# BlueStone_Terminal_V2_11.net
KiCad netlist of a schematic drawn in Altium Designer
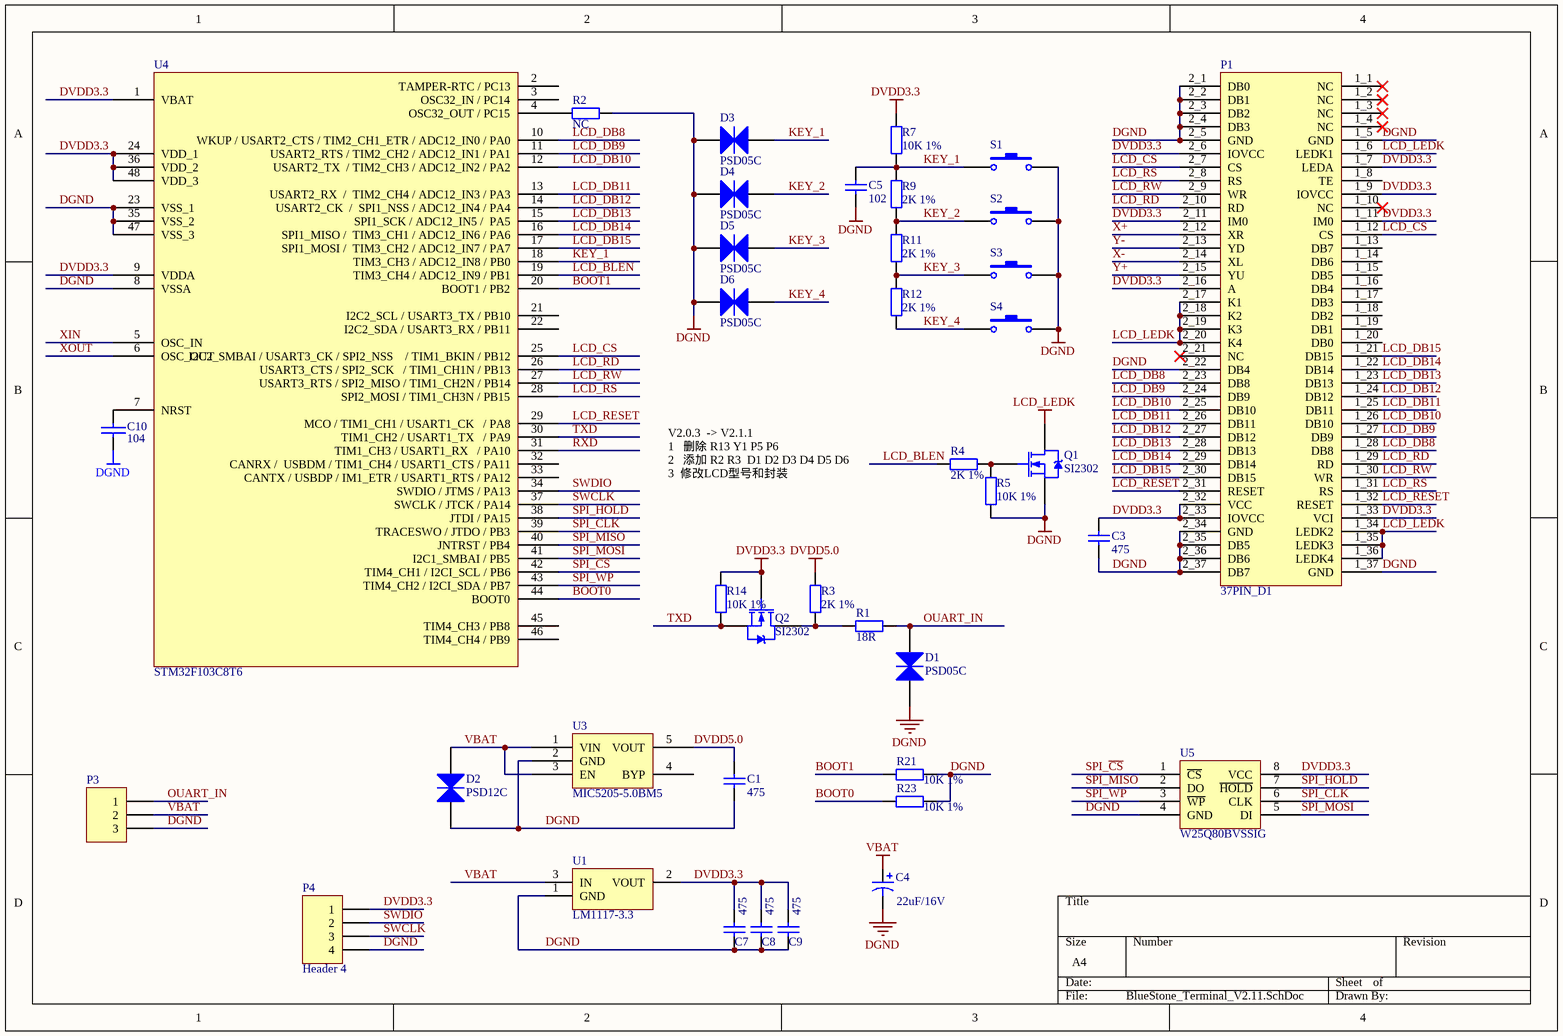
[diagram p0: BlueStone_Terminal_V2.11.SchDoc]

(export (version "E")
  (design (tool "Eeschema 10.0.6"))
  (components
    (comp (ref "C1")
      (value "475")
      (footprint "1608(0603C)")
      (description "Capacitor")
      (fields (field (name "PUBLISHER") "Altium Limited"))
      (libsource (lib "Miscellaneous Devices") (part "Cap"))
    )
    (comp (ref "C3")
      (value "475")
      (footprint "1608(0603C)")
      (description "Capacitor")
      (fields (field (name "PUBLISHER") "Altium Limited"))
      (libsource (lib "Miscellaneous Devices") (part "Cap"))
    )
    (comp (ref "C4")
      (value "22uF/16V")
      (footprint "3216(1206B)")
      (description "Polarized Capacitor (Radial)")
      (fields (field (name "PUBLISHER") "Altium Limited"))
      (libsource (lib "Miscellaneous Devices") (part "Cap Pol1"))
    )
    (comp (ref "C5")
      (value "102")
      (footprint "1608(0603C)")
      (description "Capacitor")
      (fields (field (name "PUBLISHER") "Altium Limited"))
      (libsource (lib "Miscellaneous Devices") (part "Cap"))
    )
    (comp (ref "C7")
      (value "475")
      (footprint "1608(0603C)")
      (description "Capacitor")
      (fields (field (name "PUBLISHER") "Altium Limited"))
      (libsource (lib "Miscellaneous Devices") (part "Cap"))
    )
    (comp (ref "C8")
      (value "475")
      (footprint "1608(0603C)")
      (description "Capacitor")
      (fields (field (name "PUBLISHER") "Altium Limited"))
      (libsource (lib "Miscellaneous Devices") (part "Cap"))
    )
    (comp (ref "C9")
      (value "475")
      (footprint "1608(0603C)")
      (description "Capacitor")
      (fields (field (name "PUBLISHER") "Altium Limited"))
      (libsource (lib "Miscellaneous Devices") (part "Cap"))
    )
    (comp (ref "C10")
      (value "104")
      (footprint "1608(0603C)")
      (description "Capacitor")
      (libsource (lib "*") (part "CAP"))
    )
    (comp (ref "D1")
      (value "PSD05C")
      (footprint "SOD523(0603R)")
      (description "Default Diode")
      (fields (field (name "PUBLISHER") "Altium Limited"))
      (libsource (lib "diodes") (part "RSBC6.8CS"))
    )
    (comp (ref "D2")
      (value "PSD12C")
      (footprint "SOD523(0603R)")
      (description "Default Diode")
      (fields (field (name "PUBLISHER") "Altium Limited"))
      (libsource (lib "diodes") (part "RSBC6.8CS"))
    )
    (comp (ref "D3")
      (value "PSD05C")
      (footprint "SOD523(0603R)")
      (description "Default Diode")
      (fields (field (name "PUBLISHER") "Altium Limited"))
      (libsource (lib "diodes") (part "RSBC6.8CS"))
    )
    (comp (ref "D4")
      (value "PSD05C")
      (footprint "SOD523(0603R)")
      (description "Default Diode")
      (fields (field (name "PUBLISHER") "Altium Limited"))
      (libsource (lib "diodes") (part "RSBC6.8CS"))
    )
    (comp (ref "D5")
      (value "PSD05C")
      (footprint "SOD523(0603R)")
      (description "Default Diode")
      (fields (field (name "PUBLISHER") "Altium Limited"))
      (libsource (lib "diodes") (part "RSBC6.8CS"))
    )
    (comp (ref "D6")
      (value "PSD05C")
      (footprint "SOD523(0603R)")
      (description "Default Diode")
      (fields (field (name "PUBLISHER") "Altium Limited"))
      (libsource (lib "diodes") (part "RSBC6.8CS"))
    )
    (comp (ref "P1") (value "37PIN_D1") (footprint "Z240_D1") (libsource (lib "LCD") (part "37PIN_D1")))
    (comp (ref "P3")
      (value "~")
      (footprint "SIP3")
      (description "Header, 3-Pin")
      (fields (field (name "PUBLISHER") "Altium Limited"))
      (libsource (lib "Miscellaneous Connectors") (part "Header 3"))
    )
    (comp (ref "P4")
      (value "Header 4")
      (footprint "HDR1X4")
      (description "Header, 4-Pin")
      (fields (field (name "PUBLISHER") "Altium Limited"))
      (libsource (lib "Miscellaneous Connectors") (part "Header 4"))
    )
    (comp (ref "Q1") (value "SI2302") (footprint "SOT-23") (libsource (lib "MosSCH") (part "NMOS  (SOT23)")))
    (comp (ref "Q2") (value "SI2302") (footprint "SOT-23") (libsource (lib "MosSCH") (part "NMOS  (SOT23)")))
    (comp (ref "R1")
      (value "18R")
      (footprint "1608(0603R)")
      (description "Resistor")
      (fields (field (name "PUBLISHER") "Altium Limited"))
      (libsource (lib "Miscellaneous Devices") (part "Res2"))
    )
    (comp (ref "R2")
      (value "NC")
      (footprint "1608(0603R)")
      (description "Resistor")
      (fields (field (name "PUBLISHER") "Altium Limited"))
      (libsource (lib "") (part "Res2_3"))
    )
    (comp (ref "R3")
      (value "2K 1%")
      (footprint "1608(0603R)")
      (description "Resistor")
      (fields (field (name "PUBLISHER") "Altium Limited"))
      (libsource (lib "") (part "Res2_2"))
    )
    (comp (ref "R4")
      (value "2K 1%")
      (footprint "1608(0603R)")
      (description "Resistor")
      (fields (field (name "PUBLISHER") "Altium Limited"))
      (libsource (lib "Miscellaneous Devices") (part "Res2"))
    )
    (comp (ref "R5")
      (value "10K 1%")
      (footprint "1608(0603R)")
      (description "Resistor")
      (fields (field (name "PUBLISHER") "Altium Limited"))
      (libsource (lib "") (part "Res2_2"))
    )
    (comp (ref "R7")
      (value "10K 1%")
      (footprint "1608(0603R)")
      (description "Resistor")
      (fields (field (name "PUBLISHER") "Altium Limited"))
      (libsource (lib "") (part "Res2_1"))
    )
    (comp (ref "R9")
      (value "2K 1%")
      (footprint "1608(0603R)")
      (description "Resistor")
      (fields (field (name "PUBLISHER") "Altium Limited"))
      (libsource (lib "") (part "Res2_1"))
    )
    (comp (ref "R11")
      (value "2K 1%")
      (footprint "1608(0603R)")
      (description "Resistor")
      (fields (field (name "PUBLISHER") "Altium Limited"))
      (libsource (lib "") (part "Res2_1"))
    )
    (comp (ref "R12")
      (value "2K 1%")
      (footprint "1608(0603R)")
      (description "Resistor")
      (fields (field (name "PUBLISHER") "Altium Limited"))
      (libsource (lib "") (part "Res2_1"))
    )
    (comp (ref "R14")
      (value "10K 1%")
      (footprint "1608(0603R)")
      (description "Resistor")
      (fields (field (name "PUBLISHER") "Altium Limited"))
      (libsource (lib "") (part "Res2_2"))
    )
    (comp (ref "R21")
      (value "10K 1%")
      (footprint "1608(0603R)")
      (description "Resistor")
      (fields (field (name "PUBLISHER") "Altium Limited"))
      (libsource (lib "") (part "Res2_3"))
    )
    (comp (ref "R23")
      (value "10K 1%")
      (footprint "1608(0603R)")
      (description "Resistor")
      (fields (field (name "PUBLISHER") "Altium Limited"))
      (libsource (lib "") (part "Res2_3"))
    )
    (comp (ref "S1")
      (value "~")
      (footprint "KEY-3")
      (description "Switch")
      (fields (field (name "PUBLISHER") "Altium Limited"))
      (libsource (lib "Miscellaneous Devices") (part "SW-PB"))
    )
    (comp (ref "S2")
      (value "~")
      (footprint "KEY-3")
      (description "Switch")
      (fields (field (name "PUBLISHER") "Altium Limited"))
      (libsource (lib "Miscellaneous Devices") (part "SW-PB"))
    )
    (comp (ref "S3")
      (value "~")
      (footprint "KEY-3")
      (description "Switch")
      (fields (field (name "PUBLISHER") "Altium Limited"))
      (libsource (lib "Miscellaneous Devices") (part "SW-PB"))
    )
    (comp (ref "S4")
      (value "~")
      (footprint "KEY-3")
      (description "Switch")
      (fields (field (name "PUBLISHER") "Altium Limited"))
      (libsource (lib "Miscellaneous Devices") (part "SW-PB"))
    )
    (comp (ref "U1") (value "LM1117-3.3") (footprint "SOT-223") (libsource (lib "power") (part "LM1117")))
    (comp (ref "U3")
      (value "MIC5205-5.0BM5")
      (footprint "SOT23-5")
      (libsource (lib "power") (part "MIC5205"))
    )
    (comp (ref "U4") (value "STM32F103C8T6") (footprint "LQFP48_N") (libsource (lib "*") (part "STM32F103C")))
    (comp (ref "U5")
      (value "W25Q80BVSSIG")
      (footprint "SO-8(Width: 7.8mm)")
      (libsource (lib "MySCH") (part "W55X16"))
    )
  )
  (nets
    (net (code "1") (name "/BOOT0") (class "Default")
      (node (ref "R23") (pin "1") (pinfunction "1_1") (pintype "passive"))
      (node (ref "U4") (pin "44") (pinfunction "BOOT0_44") (pintype "passive"))
    )
    (net (code "2") (name "/BOOT1") (class "Default")
      (node (ref "R21") (pin "1") (pinfunction "1_1") (pintype "passive"))
      (node (ref "U4") (pin "20") (pinfunction "BOOT1_/_PB2_20") (pintype "passive"))
    )
    (net (code "3") (name "/KEY_1") (class "Default")
      (node (ref "C5") (pin "1") (pinfunction "1_1") (pintype "passive"))
      (node (ref "D3") (pin "2") (pinfunction "K_2") (pintype "passive"))
      (node (ref "R7") (pin "2") (pinfunction "2_2") (pintype "passive"))
      (node (ref "R9") (pin "1") (pinfunction "1_1") (pintype "passive"))
      (node (ref "S1") (pin "1") (pinfunction "1_1") (pintype "passive"))
      (node (ref "U4") (pin "18") (pinfunction "TIM3_CH3_/_ADC12_IN8_/_PB0_18") (pintype "passive"))
    )
    (net (code "4") (name "/KEY_2") (class "Default")
      (node (ref "D4") (pin "2") (pinfunction "K_2") (pintype "passive"))
      (node (ref "R11") (pin "1") (pinfunction "1_1") (pintype "passive"))
      (node (ref "R9") (pin "2") (pinfunction "2_2") (pintype "passive"))
      (node (ref "S2") (pin "1") (pinfunction "1_1") (pintype "passive"))
    )
    (net (code "5") (name "/KEY_3") (class "Default")
      (node (ref "D5") (pin "2") (pinfunction "K_2") (pintype "passive"))
      (node (ref "R11") (pin "2") (pinfunction "2_2") (pintype "passive"))
      (node (ref "R12") (pin "1") (pinfunction "1_1") (pintype "passive"))
      (node (ref "S3") (pin "1") (pinfunction "1_1") (pintype "passive"))
    )
    (net (code "6") (name "/KEY_4") (class "Default")
      (node (ref "D6") (pin "2") (pinfunction "K_2") (pintype "passive"))
      (node (ref "R12") (pin "2") (pinfunction "2_2") (pintype "passive"))
      (node (ref "S4") (pin "1") (pinfunction "1_1") (pintype "passive"))
    )
    (net (code "7") (name "/LCD_BLEN") (class "Default")
      (node (ref "R4") (pin "2") (pinfunction "2_2") (pintype "passive"))
      (node (ref "U4") (pin "19") (pinfunction "TIM3_CH4_/_ADC12_IN9_/_PB1_19") (pintype "passive"))
    )
    (net (code "8") (name "/LCD_CS") (class "Default")
      (node (ref "P1") (pin "1_12") (pinfunction "CS_1_12") (pintype "passive"))
      (node (ref "P1") (pin "2_7") (pinfunction "CS_2_7") (pintype "passive"))
      (node (ref "U4") (pin "25") (pinfunction "I2C2_SMBAI_/_USART3_CK_/_SPI2_NSS____/_TIM1_BKIN_/_PB12_25") (pintype "passive"))
    )
    (net (code "9") (name "/LCD_DB8") (class "Default")
      (node (ref "P1") (pin "1_28") (pinfunction "DB8_1_28") (pintype "passive"))
      (node (ref "P1") (pin "2_23") (pinfunction "DB8_2_23") (pintype "passive"))
      (node (ref "U4") (pin "10") (pinfunction "WKUP_/_USART2_CTS_/_TIM2_CH1_ETR_/_ADC12_IN0_/_PA0_10") (pintype "passive"))
    )
    (net (code "10") (name "/LCD_DB9") (class "Default")
      (node (ref "P1") (pin "1_27") (pinfunction "DB9_1_27") (pintype "passive"))
      (node (ref "P1") (pin "2_24") (pinfunction "DB9_2_24") (pintype "passive"))
      (node (ref "U4") (pin "11") (pinfunction "USART2_RTS_/_TIM2_CH2_/_ADC12_IN1_/_PA1_11") (pintype "passive"))
    )
    (net (code "11") (name "/LCD_DB10") (class "Default")
      (node (ref "P1") (pin "1_26") (pinfunction "DB10_1_26") (pintype "passive"))
      (node (ref "P1") (pin "2_25") (pinfunction "DB10_2_25") (pintype "passive"))
      (node (ref "U4") (pin "12") (pinfunction "USART2_TX__/_TIM2_CH3_/_ADC12_IN2_/_PA2_12") (pintype "passive"))
    )
    (net (code "12") (name "/LCD_DB11") (class "Default")
      (node (ref "P1") (pin "1_25") (pinfunction "DB11_1_25") (pintype "passive"))
      (node (ref "P1") (pin "2_26") (pinfunction "DB11_2_26") (pintype "passive"))
      (node (ref "U4") (pin "13") (pinfunction "USART2_RX__/__TIM2_CH4_/_ADC12_IN3_/_PA3_13") (pintype "passive"))
    )
    (net (code "13") (name "/LCD_DB12") (class "Default")
      (node (ref "P1") (pin "1_24") (pinfunction "DB12_1_24") (pintype "passive"))
      (node (ref "P1") (pin "2_27") (pinfunction "DB12_2_27") (pintype "passive"))
      (node (ref "U4") (pin "14") (pinfunction "USART2_CK__/__SPI1_NSS_/_ADC12_IN4_/_PA4_14") (pintype "passive"))
    )
    (net (code "14") (name "/LCD_DB13") (class "Default")
      (node (ref "P1") (pin "1_23") (pinfunction "DB13_1_23") (pintype "passive"))
      (node (ref "P1") (pin "2_28") (pinfunction "DB13_2_28") (pintype "passive"))
      (node (ref "U4") (pin "15") (pinfunction "SPI1_SCK_/_ADC12_IN5_/__PA5_15") (pintype "passive"))
    )
    (net (code "15") (name "/LCD_DB14") (class "Default")
      (node (ref "P1") (pin "1_22") (pinfunction "DB14_1_22") (pintype "passive"))
      (node (ref "P1") (pin "2_29") (pinfunction "DB14_2_29") (pintype "passive"))
      (node (ref "U4") (pin "16") (pinfunction "SPI1_MISO_/__TIM3_CH1_/_ADC12_IN6_/_PA6_16") (pintype "passive"))
    )
    (net (code "16") (name "/LCD_DB15") (class "Default")
      (node (ref "P1") (pin "1_21") (pinfunction "DB15_1_21") (pintype "passive"))
      (node (ref "P1") (pin "2_30") (pinfunction "DB15_2_30") (pintype "passive"))
      (node (ref "U4") (pin "17") (pinfunction "SPI1_MOSI_/__TIM3_CH2_/_ADC12_IN7_/_PA7_17") (pintype "passive"))
    )
    (net (code "17") (name "/LCD_RD") (class "Default")
      (node (ref "P1") (pin "1_29") (pinfunction "RD_1_29") (pintype "passive"))
      (node (ref "P1") (pin "2_10") (pinfunction "RD_2_10") (pintype "passive"))
      (node (ref "U4") (pin "26") (pinfunction "USART3_CTS_/_SPI2_SCK___/_TIM1_CH1N_/_PB13_26") (pintype "passive"))
    )
    (net (code "18") (name "/LCD_RESET") (class "Default")
      (node (ref "P1") (pin "1_32") (pinfunction "RESET_1_32") (pintype "passive"))
      (node (ref "P1") (pin "2_31") (pinfunction "RESET_2_31") (pintype "passive"))
      (node (ref "U4") (pin "29") (pinfunction "MCO_/_TIM1_CH1_/_USART1_CK___/_PA8_29") (pintype "passive"))
    )
    (net (code "19") (name "/LCD_RS") (class "Default")
      (node (ref "P1") (pin "1_31") (pinfunction "RS_1_31") (pintype "passive"))
      (node (ref "P1") (pin "2_8") (pinfunction "RS_2_8") (pintype "passive"))
      (node (ref "U4") (pin "28") (pinfunction "SPI2_MOSI_/_TIM1_CH3N_/_PB15_28") (pintype "passive"))
    )
    (net (code "20") (name "/LCD_RW") (class "Default")
      (node (ref "P1") (pin "1_30") (pinfunction "WR_1_30") (pintype "passive"))
      (node (ref "P1") (pin "2_9") (pinfunction "WR_2_9") (pintype "passive"))
      (node (ref "U4") (pin "27") (pinfunction "USART3_RTS_/_SPI2_MISO_/_TIM1_CH2N_/_PB14_27") (pintype "passive"))
    )
    (net (code "21") (name "/OUART_IN") (class "Default")
      (node (ref "D1") (pin "2") (pinfunction "K_2") (pintype "passive"))
      (node (ref "P3") (pin "1") (pinfunction "1_1") (pintype "passive"))
      (node (ref "R1") (pin "1") (pinfunction "1_1") (pintype "passive"))
    )
    (net (code "22") (name "/RXD") (class "Default")
      (node (ref "U4") (pin "31") (pinfunction "TIM1_CH3_/_USART1_RX___/_PA10_31") (pintype "passive"))
    )
    (net (code "23") (name "/SPI_CLK") (class "Default")
      (node (ref "U4") (pin "39") (pinfunction "TRACESWO_/_JTDO_/_PB3_39") (pintype "passive"))
      (node (ref "U5") (pin "6") (pinfunction "CLK_6") (pintype "passive"))
    )
    (net (code "24") (name "/SPI_HOLD") (class "Default")
      (node (ref "U4") (pin "38") (pinfunction "JTDI_/_PA15_38") (pintype "passive"))
      (node (ref "U5") (pin "7") (pinfunction "~{HOLD}_7") (pintype "passive"))
    )
    (net (code "25") (name "/SPI_MISO") (class "Default")
      (node (ref "U4") (pin "40") (pinfunction "JNTRST_/_PB4_40") (pintype "passive"))
      (node (ref "U5") (pin "2") (pinfunction "DO_2") (pintype "passive"))
    )
    (net (code "26") (name "/SPI_MOSI") (class "Default")
      (node (ref "U4") (pin "41") (pinfunction "I2C1_SMBAI_/_PB5_41") (pintype "passive"))
      (node (ref "U5") (pin "5") (pinfunction "DI_5") (pintype "passive"))
    )
    (net (code "27") (name "/SPI_WP") (class "Default")
      (node (ref "U4") (pin "43") (pinfunction "TIM4_CH2_/_I2CI_SDA_/_PB7_43") (pintype "passive"))
      (node (ref "U5") (pin "3") (pinfunction "~{WP}_3") (pintype "passive"))
    )
    (net (code "28") (name "/SPI_~{CS}") (class "Default")
      (node (ref "U4") (pin "42") (pinfunction "TIM4_CH1_/_I2CI_SCL_/_PB6_42") (pintype "passive"))
      (node (ref "U5") (pin "1") (pinfunction "~{CS}_1") (pintype "passive"))
    )
    (net (code "29") (name "/SWCLK") (class "Default")
      (node (ref "P4") (pin "3") (pinfunction "3_3") (pintype "passive"))
      (node (ref "U4") (pin "37") (pinfunction "SWCLK_/_JTCK_/_PA14_37") (pintype "passive"))
    )
    (net (code "30") (name "/SWDIO") (class "Default")
      (node (ref "P4") (pin "2") (pinfunction "2_2") (pintype "passive"))
      (node (ref "U4") (pin "34") (pinfunction "SWDIO_/_JTMS_/_PA13_34") (pintype "passive"))
    )
    (net (code "31") (name "/TXD") (class "Default")
      (node (ref "Q2") (pin "2") (pinfunction "S_2") (pintype "passive"))
      (node (ref "R14") (pin "1") (pinfunction "1_1") (pintype "passive"))
      (node (ref "U4") (pin "30") (pinfunction "TIM1_CH2_/_USART1_TX___/_PA9_30") (pintype "passive"))
    )
    (net (code "32") (name "/X+") (class "Default")
      (node (ref "P1") (pin "2_12") (pinfunction "XR_2_12") (pintype "passive"))
    )
    (net (code "33") (name "/X-") (class "Default")
      (node (ref "P1") (pin "2_14") (pinfunction "XL_2_14") (pintype "passive"))
    )
    (net (code "34") (name "/XIN") (class "Default")
      (node (ref "U4") (pin "5") (pinfunction "OSC_IN_5") (pintype "passive"))
    )
    (net (code "35") (name "/XOUT") (class "Default")
      (node (ref "U4") (pin "6") (pinfunction "OSC_OUT_6") (pintype "passive"))
    )
    (net (code "36") (name "/Y+") (class "Default")
      (node (ref "P1") (pin "2_15") (pinfunction "YU_2_15") (pintype "passive"))
    )
    (net (code "37") (name "/Y-") (class "Default")
      (node (ref "P1") (pin "2_13") (pinfunction "YD_2_13") (pintype "passive"))
    )
    (net (code "38") (name "DGND") (class "Default")
      (node (ref "C1") (pin "2") (pinfunction "2_2") (pintype "passive"))
      (node (ref "C10") (pin "2") (pinfunction "2_2") (pintype "passive"))
      (node (ref "C3") (pin "2") (pinfunction "2_2") (pintype "passive"))
      (node (ref "C4") (pin "2") (pinfunction "2_2") (pintype "passive"))
      (node (ref "C5") (pin "2") (pinfunction "2_2") (pintype "passive"))
      (node (ref "C7") (pin "2") (pinfunction "2_2") (pintype "passive"))
      (node (ref "C8") (pin "2") (pinfunction "2_2") (pintype "passive"))
      (node (ref "C9") (pin "2") (pinfunction "2_2") (pintype "passive"))
      (node (ref "D1") (pin "1") (pinfunction "A_1") (pintype "passive"))
      (node (ref "D2") (pin "1") (pinfunction "A_1") (pintype "passive"))
      (node (ref "D3") (pin "1") (pinfunction "A_1") (pintype "passive"))
      (node (ref "D4") (pin "1") (pinfunction "A_1") (pintype "passive"))
      (node (ref "D5") (pin "1") (pinfunction "A_1") (pintype "passive"))
      (node (ref "D6") (pin "1") (pinfunction "A_1") (pintype "passive"))
      (node (ref "P1") (pin "1_37") (pinfunction "GND_1_37") (pintype "passive"))
      (node (ref "P1") (pin "1_5") (pinfunction "GND_1_5") (pintype "passive"))
      (node (ref "P1") (pin "2_1") (pinfunction "DB0_2_1") (pintype "passive"))
      (node (ref "P1") (pin "2_2") (pinfunction "DB1_2_2") (pintype "passive"))
      (node (ref "P1") (pin "2_22") (pinfunction "DB4_2_22") (pintype "passive"))
      (node (ref "P1") (pin "2_3") (pinfunction "DB2_2_3") (pintype "passive"))
      (node (ref "P1") (pin "2_34") (pinfunction "GND_2_34") (pintype "passive"))
      (node (ref "P1") (pin "2_35") (pinfunction "DB5_2_35") (pintype "passive"))
      (node (ref "P1") (pin "2_36") (pinfunction "DB6_2_36") (pintype "passive"))
      (node (ref "P1") (pin "2_37") (pinfunction "DB7_2_37") (pintype "passive"))
      (node (ref "P1") (pin "2_4") (pinfunction "DB3_2_4") (pintype "passive"))
      (node (ref "P1") (pin "2_5") (pinfunction "GND_2_5") (pintype "passive"))
      (node (ref "P3") (pin "3") (pinfunction "3_3") (pintype "passive"))
      (node (ref "P4") (pin "4") (pinfunction "4_4") (pintype "passive"))
      (node (ref "Q1") (pin "2") (pinfunction "S_2") (pintype "passive"))
      (node (ref "R2") (pin "2") (pinfunction "2_2") (pintype "passive"))
      (node (ref "R21") (pin "2") (pinfunction "2_2") (pintype "passive"))
      (node (ref "R23") (pin "2") (pinfunction "2_2") (pintype "passive"))
      (node (ref "R5") (pin "1") (pinfunction "1_1") (pintype "passive"))
      (node (ref "S1") (pin "2") (pinfunction "2_2") (pintype "passive"))
      (node (ref "S2") (pin "2") (pinfunction "2_2") (pintype "passive"))
      (node (ref "S3") (pin "2") (pinfunction "2_2") (pintype "passive"))
      (node (ref "S4") (pin "2") (pinfunction "2_2") (pintype "passive"))
      (node (ref "U1") (pin "1") (pinfunction "GND_1") (pintype "passive"))
      (node (ref "U3") (pin "2") (pinfunction "GND_2") (pintype "passive"))
      (node (ref "U4") (pin "23") (pinfunction "VSS_1_23") (pintype "passive"))
      (node (ref "U4") (pin "35") (pinfunction "VSS_2_35") (pintype "passive"))
      (node (ref "U4") (pin "47") (pinfunction "VSS_3_47") (pintype "passive"))
      (node (ref "U4") (pin "8") (pinfunction "VSSA_8") (pintype "passive"))
      (node (ref "U5") (pin "4") (pinfunction "GND_4") (pintype "passive"))
    )
    (net (code "39") (name "DVDD3.3") (class "Default")
      (node (ref "C3") (pin "1") (pinfunction "1_1") (pintype "passive"))
      (node (ref "C7") (pin "1") (pinfunction "1_1") (pintype "passive"))
      (node (ref "C8") (pin "1") (pinfunction "1_1") (pintype "passive"))
      (node (ref "C9") (pin "1") (pinfunction "1_1") (pintype "passive"))
      (node (ref "P1") (pin "1_11") (pinfunction "IM0_1_11") (pintype "passive"))
      (node (ref "P1") (pin "1_33") (pinfunction "VCI_1_33") (pintype "passive"))
      (node (ref "P1") (pin "1_7") (pinfunction "LEDA_1_7") (pintype "passive"))
      (node (ref "P1") (pin "1_9") (pinfunction "IOVCC_1_9") (pintype "passive"))
      (node (ref "P1") (pin "2_11") (pinfunction "IM0_2_11") (pintype "passive"))
      (node (ref "P1") (pin "2_16") (pinfunction "A_2_16") (pintype "passive"))
      (node (ref "P1") (pin "2_32") (pinfunction "VCC_2_32") (pintype "passive"))
      (node (ref "P1") (pin "2_33") (pinfunction "IOVCC_2_33") (pintype "passive"))
      (node (ref "P1") (pin "2_6") (pinfunction "IOVCC_2_6") (pintype "passive"))
      (node (ref "P4") (pin "1") (pinfunction "1_1") (pintype "passive"))
      (node (ref "Q2") (pin "1") (pinfunction "G_1") (pintype "passive"))
      (node (ref "R14") (pin "2") (pinfunction "2_2") (pintype "passive"))
      (node (ref "R7") (pin "1") (pinfunction "1_1") (pintype "passive"))
      (node (ref "U1") (pin "2") (pinfunction "VOUT_2") (pintype "passive"))
      (node (ref "U4") (pin "1") (pinfunction "VBAT_1") (pintype "passive"))
      (node (ref "U4") (pin "24") (pinfunction "VDD_1_24") (pintype "passive"))
      (node (ref "U4") (pin "36") (pinfunction "VDD_2_36") (pintype "passive"))
      (node (ref "U4") (pin "48") (pinfunction "VDD_3_48") (pintype "passive"))
      (node (ref "U4") (pin "9") (pinfunction "VDDA_9") (pintype "passive"))
      (node (ref "U5") (pin "8") (pinfunction "VCC_8") (pintype "passive"))
    )
    (net (code "40") (name "DVDD5.0") (class "Default")
      (node (ref "C1") (pin "1") (pinfunction "1_1") (pintype "passive"))
      (node (ref "R3") (pin "2") (pinfunction "2_2") (pintype "passive"))
      (node (ref "U3") (pin "5") (pinfunction "VOUT_5") (pintype "passive"))
    )
    (net (code "41") (name "LCD_LEDK") (class "Default")
      (node (ref "P1") (pin "1_34") (pinfunction "LEDK2_1_34") (pintype "passive"))
      (node (ref "P1") (pin "1_35") (pinfunction "LEDK3_1_35") (pintype "passive"))
      (node (ref "P1") (pin "1_36") (pinfunction "LEDK4_1_36") (pintype "passive"))
      (node (ref "P1") (pin "1_6") (pinfunction "LEDK1_1_6") (pintype "passive"))
      (node (ref "P1") (pin "2_17") (pinfunction "K1_2_17") (pintype "passive"))
      (node (ref "P1") (pin "2_18") (pinfunction "K2_2_18") (pintype "passive"))
      (node (ref "P1") (pin "2_19") (pinfunction "K3_2_19") (pintype "passive"))
      (node (ref "P1") (pin "2_20") (pinfunction "K4_2_20") (pintype "passive"))
      (node (ref "Q1") (pin "3") (pinfunction "D_3") (pintype "passive"))
    )
    (net (code "42") (name "Net-(Q1-G)") (class "Default")
      (node (ref "Q1") (pin "1") (pinfunction "G_1") (pintype "passive"))
      (node (ref "R4") (pin "1") (pinfunction "1_1") (pintype "passive"))
      (node (ref "R5") (pin "2") (pinfunction "2_2") (pintype "passive"))
    )
    (net (code "43") (name "Net-(Q2-D)") (class "Default")
      (node (ref "Q2") (pin "3") (pinfunction "D_3") (pintype "passive"))
      (node (ref "R1") (pin "2") (pinfunction "2_2") (pintype "passive"))
      (node (ref "R3") (pin "1") (pinfunction "1_1") (pintype "passive"))
    )
    (net (code "44") (name "Net-(U4-NRST)") (class "Default")
      (node (ref "C10") (pin "1") (pinfunction "1_1") (pintype "passive"))
      (node (ref "U4") (pin "7") (pinfunction "NRST_7") (pintype "passive"))
    )
    (net (code "45") (name "Net-(U4-OSC32_OUT_{slash}_PC15)") (class "Default")
      (node (ref "R2") (pin "1") (pinfunction "1_1") (pintype "passive"))
      (node (ref "U4") (pin "4") (pinfunction "OSC32_OUT_/_PC15_4") (pintype "passive"))
    )
    (net (code "46") (name "VBAT") (class "Default")
      (node (ref "C4") (pin "1") (pinfunction "1_1") (pintype "passive"))
      (node (ref "D2") (pin "2") (pinfunction "K_2") (pintype "passive"))
      (node (ref "P3") (pin "2") (pinfunction "2_2") (pintype "passive"))
      (node (ref "U1") (pin "3") (pinfunction "IN_3") (pintype "passive"))
      (node (ref "U3") (pin "1") (pinfunction "VIN_1") (pintype "passive"))
      (node (ref "U3") (pin "3") (pinfunction "EN_3") (pintype "passive"))
    )
    (net (code "47") (name "unconnected-(P1-DB0-Pad1_20)") (class "Default")
      (node (ref "P1") (pin "1_20") (pinfunction "DB0_1_20") (pintype "passive"))
    )
    (net (code "48") (name "unconnected-(P1-DB1-Pad1_19)") (class "Default")
      (node (ref "P1") (pin "1_19") (pinfunction "DB1_1_19") (pintype "passive"))
    )
    (net (code "49") (name "unconnected-(P1-DB2-Pad1_18)") (class "Default")
      (node (ref "P1") (pin "1_18") (pinfunction "DB2_1_18") (pintype "passive"))
    )
    (net (code "50") (name "unconnected-(P1-DB3-Pad1_17)") (class "Default")
      (node (ref "P1") (pin "1_17") (pinfunction "DB3_1_17") (pintype "passive"))
    )
    (net (code "51") (name "unconnected-(P1-DB4-Pad1_16)") (class "Default")
      (node (ref "P1") (pin "1_16") (pinfunction "DB4_1_16") (pintype "passive"))
    )
    (net (code "52") (name "unconnected-(P1-DB5-Pad1_15)") (class "Default")
      (node (ref "P1") (pin "1_15") (pinfunction "DB5_1_15") (pintype "passive"))
    )
    (net (code "53") (name "unconnected-(P1-DB6-Pad1_14)") (class "Default")
      (node (ref "P1") (pin "1_14") (pinfunction "DB6_1_14") (pintype "passive"))
    )
    (net (code "54") (name "unconnected-(P1-DB7-Pad1_13)") (class "Default")
      (node (ref "P1") (pin "1_13") (pinfunction "DB7_1_13") (pintype "passive"))
    )
    (net (code "55") (name "unconnected-(P1-NC-Pad1_1)") (class "Default")
      (node (ref "P1") (pin "1_1") (pinfunction "NC_1_1") (pintype "passive+no_connect"))
    )
    (net (code "56") (name "unconnected-(P1-NC-Pad1_2)") (class "Default")
      (node (ref "P1") (pin "1_2") (pinfunction "NC_1_2") (pintype "passive+no_connect"))
    )
    (net (code "57") (name "unconnected-(P1-NC-Pad1_3)") (class "Default")
      (node (ref "P1") (pin "1_3") (pinfunction "NC_1_3") (pintype "passive+no_connect"))
    )
    (net (code "58") (name "unconnected-(P1-NC-Pad1_4)") (class "Default")
      (node (ref "P1") (pin "1_4") (pinfunction "NC_1_4") (pintype "passive+no_connect"))
    )
    (net (code "59") (name "unconnected-(P1-NC-Pad1_10)") (class "Default")
      (node (ref "P1") (pin "1_10") (pinfunction "NC_1_10") (pintype "passive+no_connect"))
    )
    (net (code "60") (name "unconnected-(P1-NC-Pad2_21)") (class "Default")
      (node (ref "P1") (pin "2_21") (pinfunction "NC_2_21") (pintype "passive+no_connect"))
    )
    (net (code "61") (name "unconnected-(P1-TE-Pad1_8)") (class "Default")
      (node (ref "P1") (pin "1_8") (pinfunction "TE_1_8") (pintype "passive"))
    )
    (net (code "62") (name "unconnected-(U3-BYP-Pad4)") (class "Default")
      (node (ref "U3") (pin "4") (pinfunction "BYP_4") (pintype "passive"))
    )
    (net (code "63") (name "unconnected-(U4-CANRX_{slash}__USBDM_{slash}_TIM1_CH4_{slash}_USART1_CTS_{slash}_PA11-Pad32)") (class "Default")
      (node (ref "U4") (pin "32") (pinfunction "CANRX_/__USBDM_/_TIM1_CH4_/_USART1_CTS_/_PA11_32") (pintype "passive"))
    )
    (net (code "64") (name "unconnected-(U4-CANTX_{slash}_USBDP_{slash}_IM1_ETR_{slash}_USART1_RTS_{slash}_PA12-Pad33)") (class "Default")
      (node (ref "U4") (pin "33") (pinfunction "CANTX_/_USBDP_/_IM1_ETR_/_USART1_RTS_/_PA12_33") (pintype "passive"))
    )
    (net (code "65") (name "unconnected-(U4-I2C2_SCL_{slash}_USART3_TX_{slash}_PB10-Pad21)") (class "Default")
      (node (ref "U4") (pin "21") (pinfunction "I2C2_SCL_/_USART3_TX_/_PB10_21") (pintype "passive"))
    )
    (net (code "66") (name "unconnected-(U4-I2C2_SDA_{slash}_USART3_RX_{slash}_PB11-Pad22)") (class "Default")
      (node (ref "U4") (pin "22") (pinfunction "I2C2_SDA_/_USART3_RX_/_PB11_22") (pintype "passive"))
    )
    (net (code "67") (name "unconnected-(U4-OSC32_IN_{slash}_PC14-Pad3)") (class "Default")
      (node (ref "U4") (pin "3") (pinfunction "OSC32_IN_/_PC14_3") (pintype "passive"))
    )
    (net (code "68") (name "unconnected-(U4-TAMPER-RTC_{slash}_PC13-Pad2)") (class "Default")
      (node (ref "U4") (pin "2") (pinfunction "TAMPER-RTC_/_PC13_2") (pintype "passive"))
    )
    (net (code "69") (name "unconnected-(U4-TIM4_CH3_{slash}_PB8-Pad45)") (class "Default")
      (node (ref "U4") (pin "45") (pinfunction "TIM4_CH3_/_PB8_45") (pintype "passive"))
    )
    (net (code "70") (name "unconnected-(U4-TIM4_CH4_{slash}_PB9-Pad46)") (class "Default")
      (node (ref "U4") (pin "46") (pinfunction "TIM4_CH4_/_PB9_46") (pintype "passive"))
    )
  )
)
